# Xbee_extension.net
KiCad netlist of a schematic drawn in EAGLE
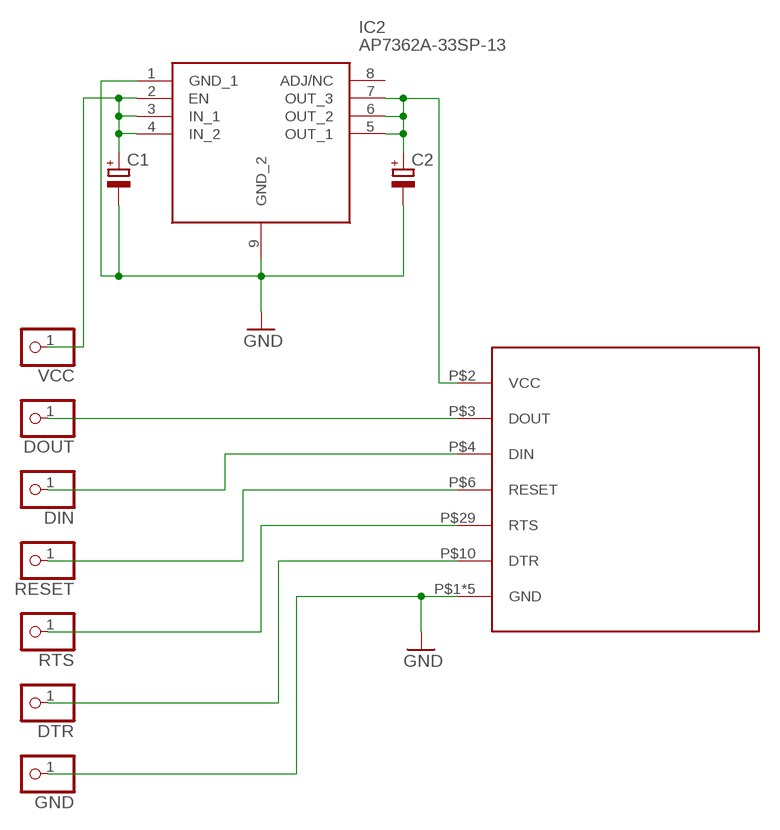
[diagram p0: schematic, sheet 1]

(export (version "E")
  (design (tool "Eeschema 10.0.6"))
  (components
    (comp (ref "C1")
      (value "CPOL-EU153CLV-0605")
      (footprint "eagle-import:153CLV-0605")
      (libsource (lib "eagle-import") (part "CPOL-EU153CLV-0605"))
    )
    (comp (ref "C2")
      (value "CPOL-EU153CLV-0605")
      (footprint "eagle-import:153CLV-0605")
      (libsource (lib "eagle-import") (part "CPOL-EU153CLV-0605"))
    )
    (comp (ref "DIN")
      (value "PINHD-1X1")
      (footprint "eagle-import:1X01")
      (libsource (lib "eagle-import") (part "PINHD-1X1"))
    )
    (comp (ref "DOUT")
      (value "PINHD-1X1")
      (footprint "eagle-import:1X01")
      (libsource (lib "eagle-import") (part "PINHD-1X1"))
    )
    (comp (ref "DTR")
      (value "PINHD-1X1")
      (footprint "eagle-import:1X01")
      (libsource (lib "eagle-import") (part "PINHD-1X1"))
    )
    (comp (ref "GND")
      (value "PINHD-1X1")
      (footprint "eagle-import:1X01")
      (libsource (lib "eagle-import") (part "PINHD-1X1"))
    )
    (comp (ref "IC2")
      (value "AP7362A-33SP-13")
      (footprint "eagle-import:SOIC127P600X150-9N")
      (fields (field (name "MOUSER_PART_NUMBER") "621-AP7362A-33SP-13"))
      (libsource (lib "eagle-import") (part "AP7362A-33SP-13"))
    )
    (comp (ref "RESET")
      (value "PINHD-1X1")
      (footprint "eagle-import:1X01")
      (libsource (lib "eagle-import") (part "PINHD-1X1"))
    )
    (comp (ref "RTS")
      (value "PINHD-1X1")
      (footprint "eagle-import:1X01")
      (libsource (lib "eagle-import") (part "PINHD-1X1"))
    )
    (comp (ref "U$1")
      (value "PRO_XTC")
      (footprint "eagle-import:PRO_XTC")
      (libsource (lib "eagle-import") (part "PRO_XTC"))
    )
    (comp (ref "VCC")
      (value "PINHD-1X1")
      (footprint "eagle-import:1X01")
      (libsource (lib "eagle-import") (part "PINHD-1X1"))
    )
  )
  (nets
    (net (code "1") (name "GND") (class "Default")
      (node (ref "C1") (pin "-") (pinfunction "-_-") (pintype "passive"))
      (node (ref "C2") (pin "-") (pinfunction "-_-") (pintype "passive"))
      (node (ref "GND") (pin "1") (pinfunction "1_1") (pintype "passive"))
      (node (ref "IC2") (pin "1") (pinfunction "GND_1_1") (pintype "bidirectional"))
      (node (ref "IC2") (pin "9") (pinfunction "GND_2_9") (pintype "bidirectional"))
      (node (ref "U$1") (pin "P$1") (pinfunction "GND_P$1") (pintype "bidirectional"))
      (node (ref "U$1") (pin "P$11") (pinfunction "GND_P$11") (pintype "bidirectional"))
      (node (ref "U$1") (pin "P$13") (pinfunction "GND_P$13") (pintype "bidirectional"))
      (node (ref "U$1") (pin "P$22") (pinfunction "GND_P$22") (pintype "bidirectional"))
      (node (ref "U$1") (pin "P$35") (pinfunction "GND_P$35") (pintype "bidirectional"))
    )
    (net (code "2") (name "Net-(IC2-EN)") (class "Default")
      (node (ref "C1") (pin "+") (pinfunction "+_+") (pintype "passive"))
      (node (ref "IC2") (pin "2") (pinfunction "EN_2") (pintype "bidirectional"))
      (node (ref "IC2") (pin "3") (pinfunction "IN_1_3") (pintype "bidirectional"))
      (node (ref "IC2") (pin "4") (pinfunction "IN_2_4") (pintype "bidirectional"))
      (node (ref "VCC") (pin "1") (pinfunction "1_1") (pintype "passive"))
    )
    (net (code "3") (name "Net-(IC2-OUT_1)") (class "Default")
      (node (ref "C2") (pin "+") (pinfunction "+_+") (pintype "passive"))
      (node (ref "IC2") (pin "5") (pinfunction "OUT_1_5") (pintype "bidirectional"))
      (node (ref "IC2") (pin "6") (pinfunction "OUT_2_6") (pintype "bidirectional"))
      (node (ref "IC2") (pin "7") (pinfunction "OUT_3_7") (pintype "bidirectional"))
      (node (ref "U$1") (pin "P$2") (pinfunction "VCC_P$2") (pintype "bidirectional"))
    )
    (net (code "4") (name "Net-(U$1-DIN)") (class "Default")
      (node (ref "DIN") (pin "1") (pinfunction "1_1") (pintype "passive"))
      (node (ref "U$1") (pin "P$4") (pinfunction "DIN_P$4") (pintype "bidirectional"))
    )
    (net (code "5") (name "Net-(U$1-DOUT)") (class "Default")
      (node (ref "DOUT") (pin "1") (pinfunction "1_1") (pintype "passive"))
      (node (ref "U$1") (pin "P$3") (pinfunction "DOUT_P$3") (pintype "bidirectional"))
    )
    (net (code "6") (name "Net-(U$1-DTR)") (class "Default")
      (node (ref "DTR") (pin "1") (pinfunction "1_1") (pintype "passive"))
      (node (ref "U$1") (pin "P$10") (pinfunction "DTR_P$10") (pintype "bidirectional"))
    )
    (net (code "7") (name "Net-(U$1-RESET)") (class "Default")
      (node (ref "RESET") (pin "1") (pinfunction "1_1") (pintype "passive"))
      (node (ref "U$1") (pin "P$6") (pinfunction "RESET_P$6") (pintype "bidirectional"))
    )
    (net (code "8") (name "Net-(U$1-RTS)") (class "Default")
      (node (ref "RTS") (pin "1") (pinfunction "1_1") (pintype "passive"))
      (node (ref "U$1") (pin "P$29") (pinfunction "RTS_P$29") (pintype "bidirectional"))
    )
    (net (code "9") (name "unconnected-(IC2-ADJ{slash}NC-Pad8)") (class "Default")
      (node (ref "IC2") (pin "8") (pinfunction "ADJ/NC_8") (pintype "bidirectional"))
    )
  )
)
